# tree.net
KiCad netlist of a schematic drawn in Altium Designer
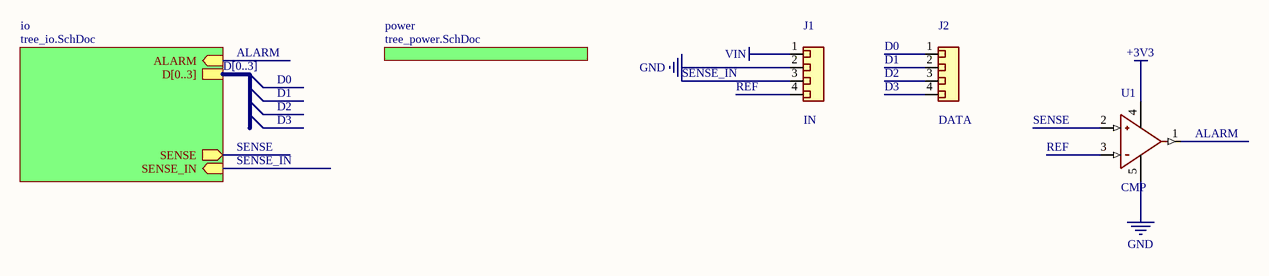
[diagram p0: tree.SchDoc]

(export (version "E")
  (design (tool "Eeschema 10.0.6"))
  (components
    (comp (ref "J1")
      (value "IN")
      (footprint "FenoliteTree:HDR1X4")
      (libsource (lib "tree") (part "Connector_4"))
    )
    (comp (ref "J2")
      (value "DATA")
      (footprint "FenoliteTree:HDR1X4")
      (libsource (lib "tree") (part "Connector_4"))
    )
    (comp (ref "U1")
      (value "CMP")
      (footprint "FenoliteTree:SOT23-5")
      (libsource (lib "tree") (part "Comparator"))
    )
  )
  (nets
    (net (code "1") (name "+3V3") (class "Default")
      (node (ref "U1") (pin "4") (pinfunction "V+_4") (pintype "power_in"))
    )
    (net (code "2") (name "/ALARM") (class "Default") (node (ref "U1") (pin "1") (pintype "output")))
    (net (code "3") (name "/D0") (class "Default")
      (node (ref "J2") (pin "1") (pinfunction "Passive_1") (pintype "passive"))
    )
    (net (code "4") (name "/D1") (class "Default")
      (node (ref "J2") (pin "2") (pinfunction "Passive_2") (pintype "passive"))
    )
    (net (code "5") (name "/D2") (class "Default")
      (node (ref "J2") (pin "3") (pinfunction "Passive_3") (pintype "passive"))
    )
    (net (code "6") (name "/D3") (class "Default")
      (node (ref "J2") (pin "4") (pinfunction "Passive_4") (pintype "passive"))
    )
    (net (code "8") (name "/REF") (class "Default")
      (node (ref "J1") (pin "4") (pinfunction "Passive_4") (pintype "passive"))
      (node (ref "U1") (pin "3") (pinfunction "-_3") (pintype "input"))
    )
    (net (code "9") (name "/SENSE") (class "Default")
      (node (ref "U1") (pin "2") (pinfunction "+_2") (pintype "input"))
    )
    (net (code "10") (name "/SENSE_IN") (class "Default")
      (node (ref "J1") (pin "3") (pinfunction "Passive_3") (pintype "passive"))
    )
    (net (code "11") (name "GND") (class "Default")
      (node (ref "J1") (pin "2") (pinfunction "Passive_2") (pintype "passive"))
      (node (ref "U1") (pin "5") (pinfunction "V-_5") (pintype "power_in"))
    )
    (net (code "12") (name "VIN") (class "Default")
      (node (ref "J1") (pin "1") (pinfunction "Passive_1") (pintype "passive"))
    )
  )
)
